# webcam.net
KiCad netlist of a schematic drawn in EAGLE
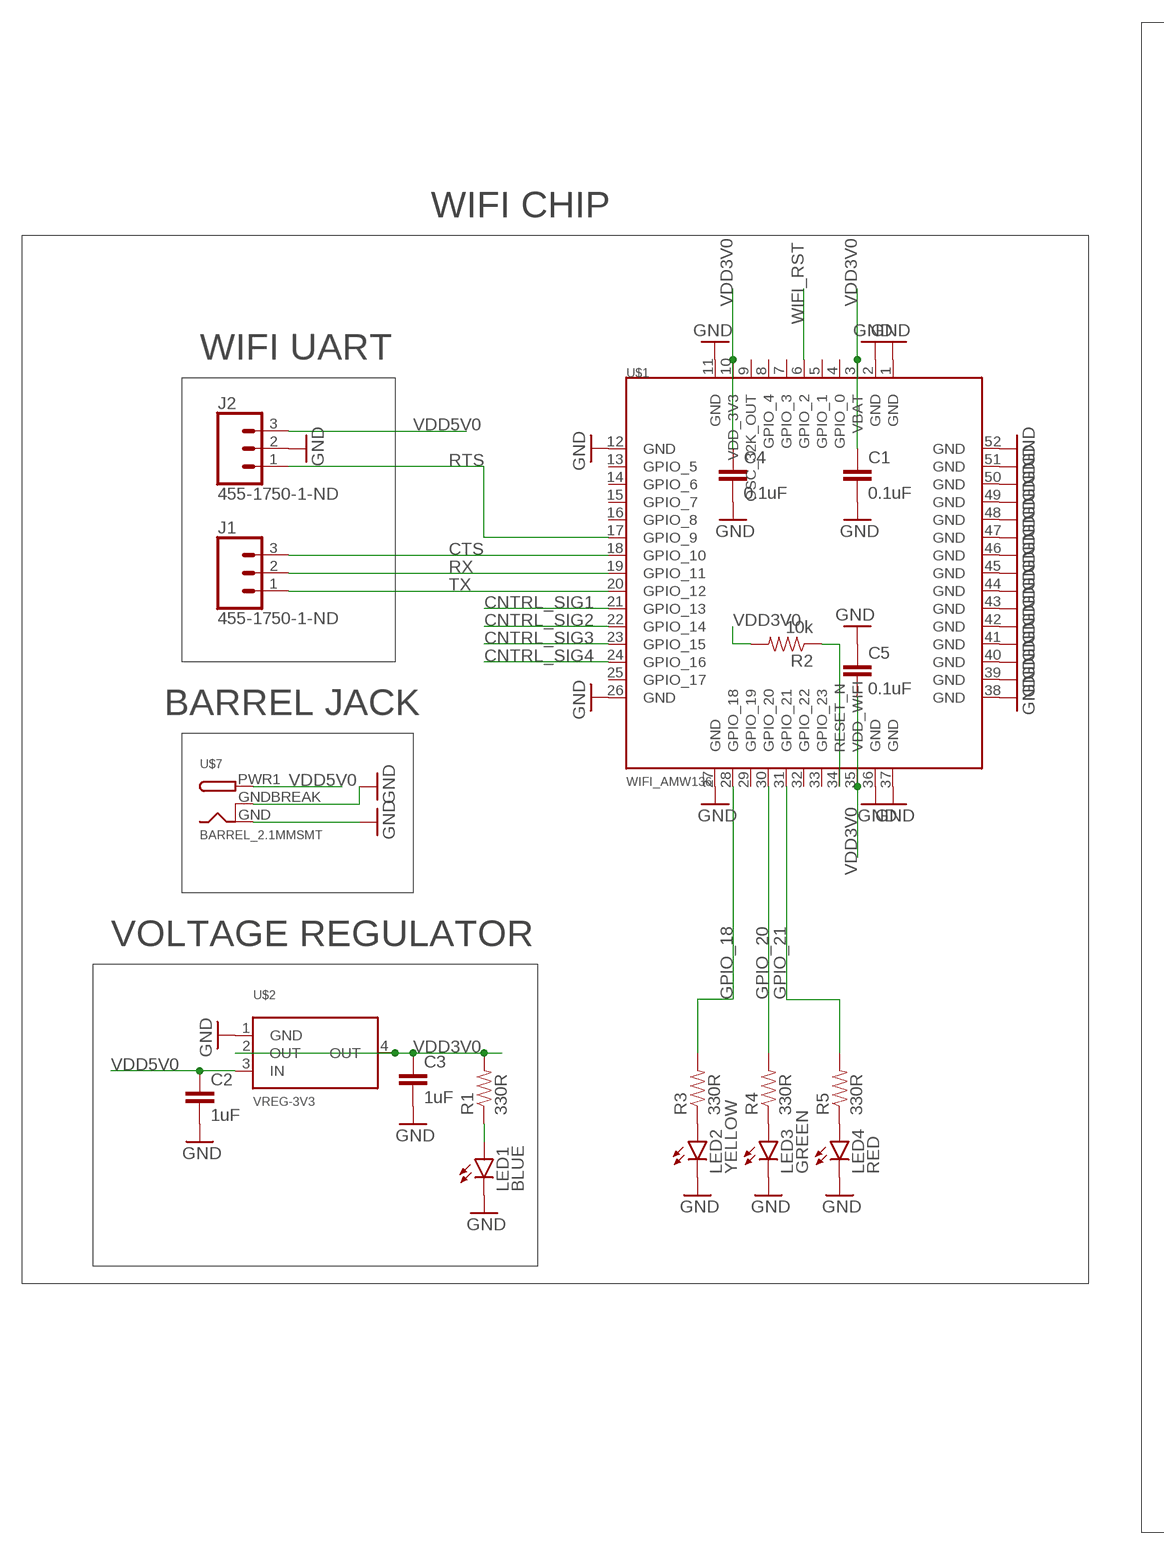
[diagram p0: schematic, sheet 1, part 1 of 2]
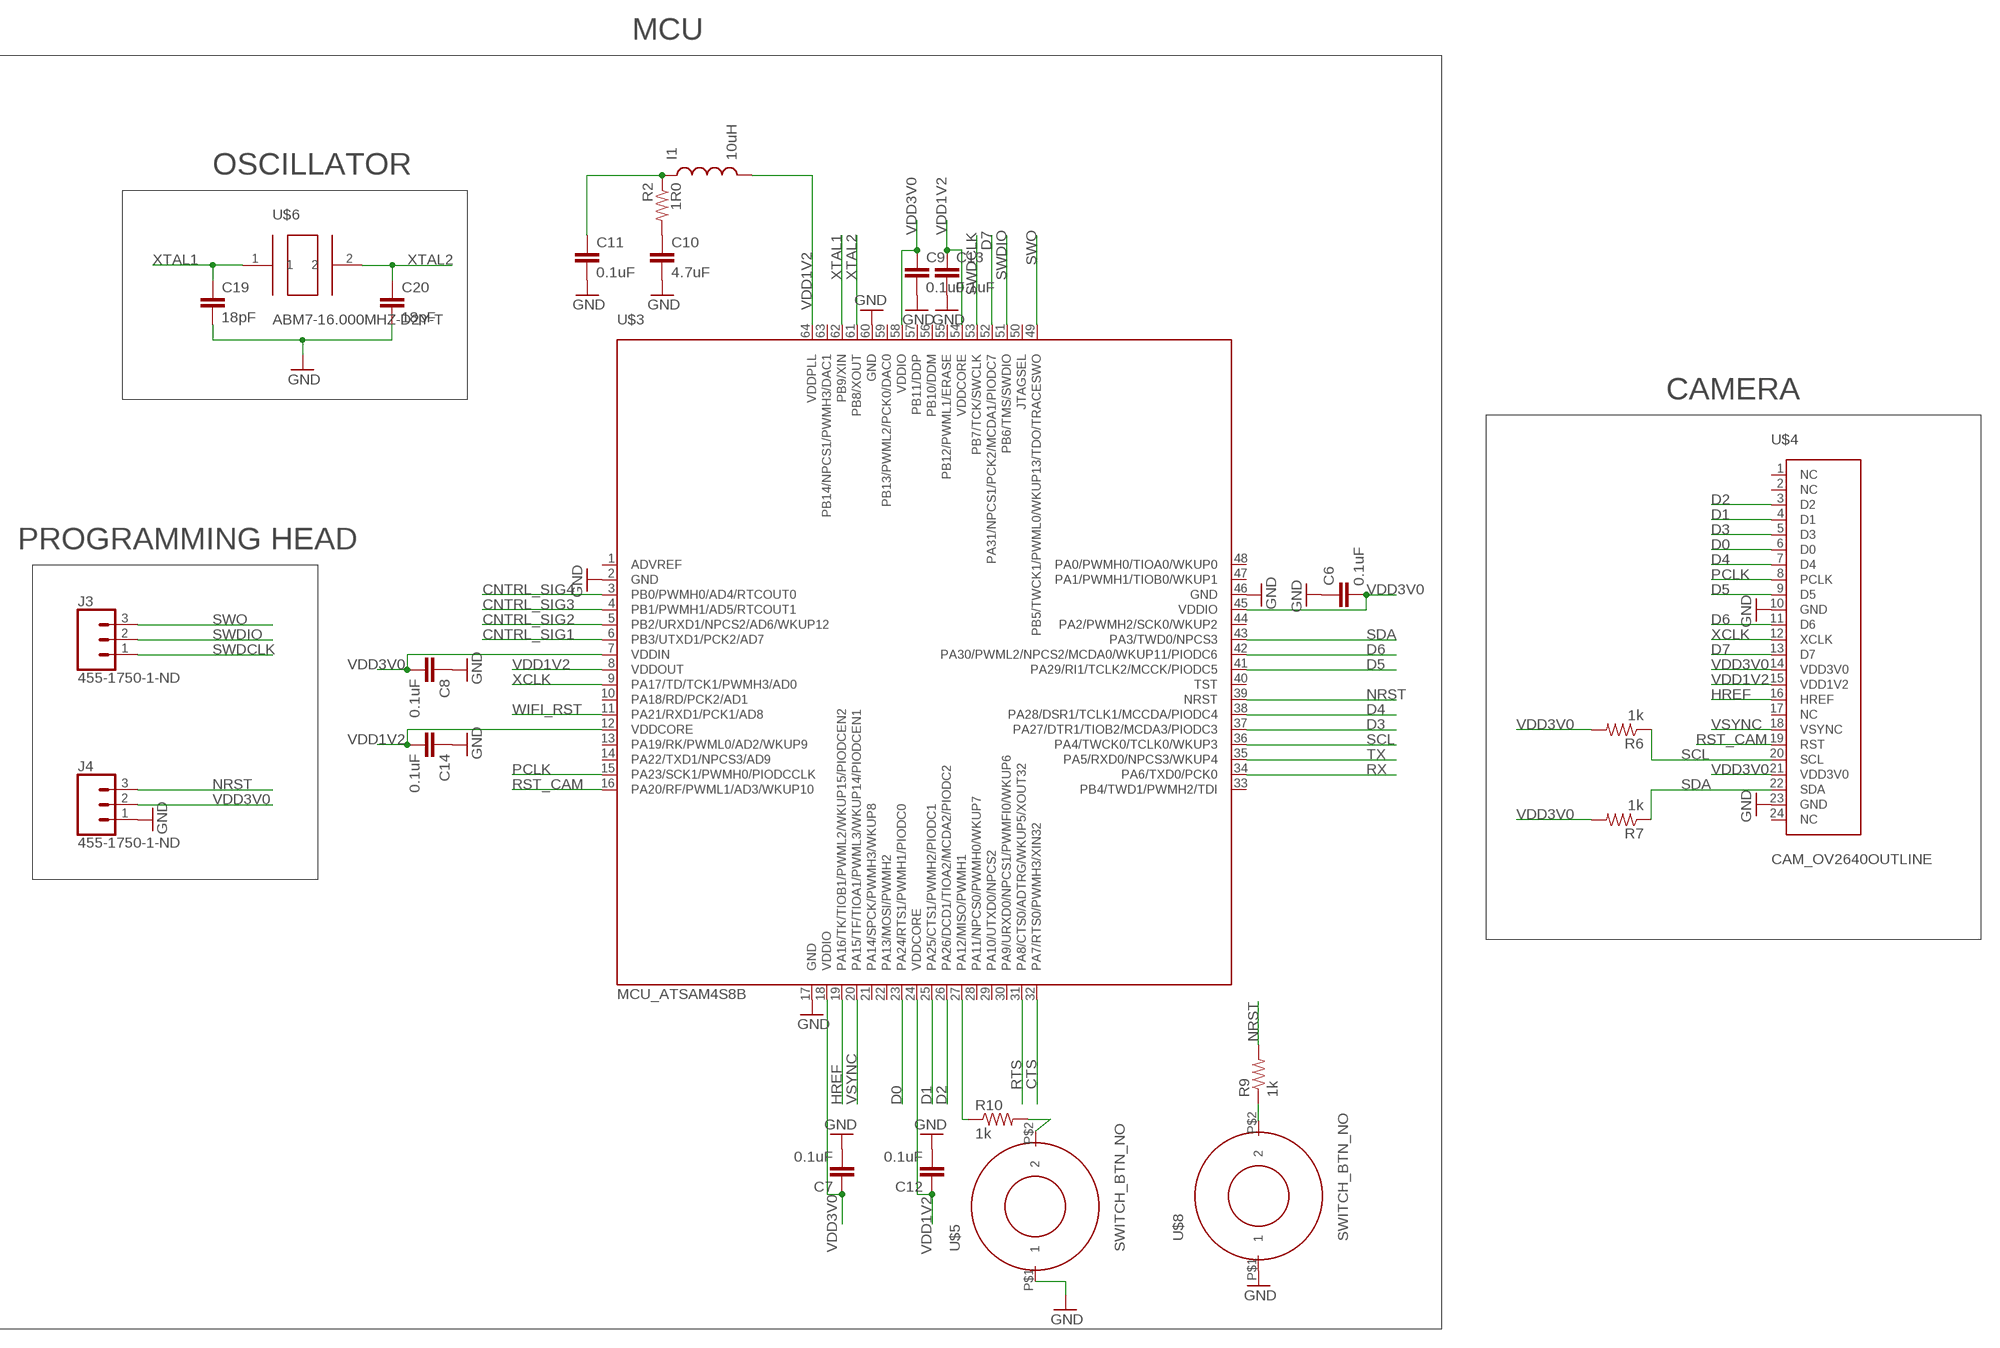
[diagram p1: schematic, sheet 1, part 2 of 2]

(export (version "E")
  (design (tool "Eeschema 10.0.6"))
  (components
    (comp (ref "1R0")
      (value "R2")
      (footprint "eagle-import:0805")
      (libsource (lib "eagle-import") (part "RES"))
    )
    (comp (ref "C1")
      (value "0.1uF")
      (footprint "eagle-import:0805")
      (libsource (lib "eagle-import") (part "CAP"))
    )
    (comp (ref "C2")
      (value "1uF")
      (footprint "eagle-import:0805")
      (libsource (lib "eagle-import") (part "CAP"))
    )
    (comp (ref "C3")
      (value "1uF")
      (footprint "eagle-import:0805")
      (libsource (lib "eagle-import") (part "CAP"))
    )
    (comp (ref "C4")
      (value "0.1uF")
      (footprint "eagle-import:0805")
      (libsource (lib "eagle-import") (part "CAP"))
    )
    (comp (ref "C5")
      (value "0.1uF")
      (footprint "eagle-import:0805")
      (libsource (lib "eagle-import") (part "CAP"))
    )
    (comp (ref "C6")
      (value "0.1uF")
      (footprint "eagle-import:0805")
      (libsource (lib "eagle-import") (part "CAP"))
    )
    (comp (ref "C7")
      (value "0.1uF")
      (footprint "eagle-import:0805")
      (libsource (lib "eagle-import") (part "CAP"))
    )
    (comp (ref "C8")
      (value "0.1uF")
      (footprint "eagle-import:0805")
      (libsource (lib "eagle-import") (part "CAP"))
    )
    (comp (ref "C9")
      (value "0.1uF")
      (footprint "eagle-import:0805")
      (libsource (lib "eagle-import") (part "CAP"))
    )
    (comp (ref "C10")
      (value "4.7uF")
      (footprint "eagle-import:0805")
      (libsource (lib "eagle-import") (part "CAP"))
    )
    (comp (ref "C11")
      (value "0.1uF")
      (footprint "eagle-import:0805")
      (libsource (lib "eagle-import") (part "CAP"))
    )
    (comp (ref "C12")
      (value "0.1uF")
      (footprint "eagle-import:0805")
      (libsource (lib "eagle-import") (part "CAP"))
    )
    (comp (ref "C13")
      (value "0.1uF")
      (footprint "eagle-import:0805")
      (libsource (lib "eagle-import") (part "CAP"))
    )
    (comp (ref "C14")
      (value "0.1uF")
      (footprint "eagle-import:0805")
      (libsource (lib "eagle-import") (part "CAP"))
    )
    (comp (ref "C19")
      (value "18pF")
      (footprint "eagle-import:0805")
      (libsource (lib "eagle-import") (part "CAP0805"))
    )
    (comp (ref "C20")
      (value "18pF")
      (footprint "eagle-import:0805")
      (libsource (lib "eagle-import") (part "CAP0805"))
    )
    (comp (ref "I1")
      (value "10uH")
      (footprint "eagle-import:0805")
      (fields (field (name "SPICEPREFIX") "I"))
      (libsource (lib "eagle-import") (part "IND"))
    )
    (comp (ref "J1")
      (value "455-1750-1-ND")
      (footprint "eagle-import:1X03")
      (libsource (lib "eagle-import") (part "CONN_03"))
    )
    (comp (ref "J2")
      (value "455-1750-1-ND")
      (footprint "eagle-import:1X03")
      (libsource (lib "eagle-import") (part "CONN_03"))
    )
    (comp (ref "J3")
      (value "455-1750-1-ND")
      (footprint "eagle-import:1X03")
      (libsource (lib "eagle-import") (part "CONN_03"))
    )
    (comp (ref "J4")
      (value "455-1750-1-ND")
      (footprint "eagle-import:1X03")
      (libsource (lib "eagle-import") (part "CONN_03"))
    )
    (comp (ref "LED1")
      (value "BLUE")
      (footprint "eagle-import:LED-0603")
      (libsource (lib "eagle-import") (part "LED0603"))
    )
    (comp (ref "LED2")
      (value "YELLOW")
      (footprint "eagle-import:LED-0603")
      (libsource (lib "eagle-import") (part "LED0603"))
    )
    (comp (ref "LED3")
      (value "GREEN")
      (footprint "eagle-import:LED-0603")
      (libsource (lib "eagle-import") (part "LED0603"))
    )
    (comp (ref "LED4")
      (value "RED")
      (footprint "eagle-import:LED-0603")
      (libsource (lib "eagle-import") (part "LED0603"))
    )
    (comp (ref "R1")
      (value "330R")
      (footprint "eagle-import:0805")
      (libsource (lib "eagle-import") (part "RES"))
    )
    (comp (ref "R2")
      (value "10k")
      (footprint "eagle-import:0805")
      (libsource (lib "eagle-import") (part "RES"))
    )
    (comp (ref "R3")
      (value "330R")
      (footprint "eagle-import:0805")
      (libsource (lib "eagle-import") (part "RES"))
    )
    (comp (ref "R4")
      (value "330R")
      (footprint "eagle-import:0805")
      (libsource (lib "eagle-import") (part "RES"))
    )
    (comp (ref "R5")
      (value "330R")
      (footprint "eagle-import:0805")
      (libsource (lib "eagle-import") (part "RES"))
    )
    (comp (ref "R6")
      (value "1k")
      (footprint "eagle-import:0805")
      (libsource (lib "eagle-import") (part "RES"))
    )
    (comp (ref "R7")
      (value "1k")
      (footprint "eagle-import:0805")
      (libsource (lib "eagle-import") (part "RES"))
    )
    (comp (ref "R9")
      (value "1k")
      (footprint "eagle-import:0805")
      (libsource (lib "eagle-import") (part "RES"))
    )
    (comp (ref "R10")
      (value "1k")
      (footprint "eagle-import:0805")
      (libsource (lib "eagle-import") (part "RES"))
    )
    (comp (ref "U$1")
      (value "WIFI_AMW136")
      (footprint "eagle-import:AMW136")
      (libsource (lib "eagle-import") (part "WIFI_AMW136"))
    )
    (comp (ref "U$2")
      (value "VREG-3V3")
      (footprint "eagle-import:R-PDSO-G4_TI")
      (libsource (lib "eagle-import") (part "VREG-3V3"))
    )
    (comp (ref "U$3")
      (value "MCU_ATSAM4S8B")
      (footprint "eagle-import:QFP50P1200X1200X160-64N")
      (libsource (lib "eagle-import") (part "MCU_ATSAM4S8B"))
    )
    (comp (ref "U$4")
      (value "CAM_OV2640OUTLINE")
      (footprint "eagle-import:CAM_CONN")
      (libsource (lib "eagle-import") (part "CAM_OV2640OUTLINE"))
    )
    (comp (ref "U$5")
      (value "SWITCH_BTN_NO")
      (footprint "eagle-import:BTN_2")
      (libsource (lib "eagle-import") (part "SWITCH_BTN_NO"))
    )
    (comp (ref "U$6")
      (value "ABM7-16.000MHZ-D2Y-T")
      (footprint "eagle-import:ABM7-16.000MHZ-D2Y-T")
      (libsource (lib "eagle-import") (part "ABM7-16.000MHZ-D2Y-T"))
    )
    (comp (ref "U$7")
      (value "BARREL_2.1MMSMT")
      (footprint "eagle-import:DCJACK_2MM_SMT")
      (libsource (lib "eagle-import") (part "BARREL_2.1MMSMT"))
    )
    (comp (ref "U$8")
      (value "SWITCH_BTN_NO")
      (footprint "eagle-import:BTN_2")
      (libsource (lib "eagle-import") (part "SWITCH_BTN_NO"))
    )
  )
  (nets
    (net (code "1") (name "/CNTRL_SIG1") (class "Default")
      (node (ref "U$1") (pin "21") (pinfunction "GPIO_13_21") (pintype "bidirectional"))
      (node (ref "U$3") (pin "6") (pinfunction "PB3/UTXD1/PCK2/AD7_6") (pintype "bidirectional"))
    )
    (net (code "2") (name "/CNTRL_SIG2") (class "Default")
      (node (ref "U$1") (pin "22") (pinfunction "GPIO_14_22") (pintype "bidirectional"))
      (node (ref "U$3") (pin "5") (pinfunction "PB2/URXD1/NPCS2/AD6/WKUP12_5") (pintype "bidirectional"))
    )
    (net (code "3") (name "/CNTRL_SIG3") (class "Default")
      (node (ref "U$1") (pin "23") (pinfunction "GPIO_15_23") (pintype "bidirectional"))
      (node (ref "U$3") (pin "4") (pinfunction "PB1/PWMH1/AD5/RTCOUT1_4") (pintype "bidirectional"))
    )
    (net (code "4") (name "/CNTRL_SIG4") (class "Default")
      (node (ref "U$1") (pin "24") (pinfunction "GPIO_16_24") (pintype "bidirectional"))
      (node (ref "U$3") (pin "3") (pinfunction "PB0/PWMH0/AD4/RTCOUT0_3") (pintype "bidirectional"))
    )
    (net (code "5") (name "/CTS") (class "Default")
      (node (ref "J1") (pin "3") (pinfunction "3_3") (pintype "passive"))
      (node (ref "U$1") (pin "18") (pinfunction "GPIO_10_18") (pintype "bidirectional"))
      (node (ref "U$3") (pin "32") (pinfunction "PA7/RTS0/PWMH3/XIN32_32") (pintype "bidirectional"))
    )
    (net (code "6") (name "/D0") (class "Default")
      (node (ref "U$3") (pin "23") (pinfunction "PA24/RTS1/PWMH1/PIODC0_23") (pintype "bidirectional"))
      (node (ref "U$4") (pin "6") (pinfunction "D0_6") (pintype "bidirectional"))
    )
    (net (code "7") (name "/D1") (class "Default")
      (node (ref "U$3") (pin "25") (pinfunction "PA25/CTS1/PWMH2/PIODC1_25") (pintype "bidirectional"))
      (node (ref "U$4") (pin "4") (pinfunction "D1_4") (pintype "bidirectional"))
    )
    (net (code "8") (name "/D2") (class "Default")
      (node (ref "U$3") (pin "26") (pinfunction "PA26/DCD1/TIOA2/MCDA2/PIODC2_26") (pintype "bidirectional"))
      (node (ref "U$4") (pin "3") (pinfunction "D2_3") (pintype "bidirectional"))
    )
    (net (code "9") (name "/D3") (class "Default")
      (node (ref "U$3") (pin "37") (pinfunction "PA27/DTR1/TIOB2/MCDA3/PIODC3_37") (pintype "bidirectional"))
      (node (ref "U$4") (pin "5") (pinfunction "D3_5") (pintype "bidirectional"))
    )
    (net (code "10") (name "/D4") (class "Default")
      (node (ref "U$3") (pin "38") (pinfunction "PA28/DSR1/TCLK1/MCCDA/PIODC4_38") (pintype "bidirectional"))
      (node (ref "U$4") (pin "7") (pinfunction "D4_7") (pintype "bidirectional"))
    )
    (net (code "11") (name "/D5") (class "Default")
      (node (ref "U$3") (pin "41") (pinfunction "PA29/RI1/TCLK2/MCCK/PIODC5_41") (pintype "bidirectional"))
      (node (ref "U$4") (pin "9") (pinfunction "D5_9") (pintype "bidirectional"))
    )
    (net (code "12") (name "/D6") (class "Default")
      (node (ref "U$3") (pin "42") (pinfunction "PA30/PWML2/NPCS2/MCDA0/WKUP11/PIODC6_42") (pintype "bidirectional"))
      (node (ref "U$4") (pin "11") (pinfunction "D6_11") (pintype "bidirectional"))
    )
    (net (code "13") (name "/D7") (class "Default")
      (node (ref "U$3") (pin "52") (pinfunction "PA31/NPCS1/PCK2/MCDA1/PIODC7_52") (pintype "bidirectional"))
      (node (ref "U$4") (pin "13") (pinfunction "D7_13") (pintype "bidirectional"))
    )
    (net (code "14") (name "/GPIO_18") (class "Default")
      (node (ref "R3") (pin "2") (pinfunction "2_2") (pintype "passive"))
      (node (ref "U$1") (pin "28") (pinfunction "GPIO_18_28") (pintype "bidirectional"))
    )
    (net (code "15") (name "/GPIO_20") (class "Default")
      (node (ref "R4") (pin "2") (pinfunction "2_2") (pintype "passive"))
      (node (ref "U$1") (pin "30") (pinfunction "GPIO_20_30") (pintype "bidirectional"))
    )
    (net (code "16") (name "/GPIO_21") (class "Default")
      (node (ref "R5") (pin "2") (pinfunction "2_2") (pintype "passive"))
      (node (ref "U$1") (pin "31") (pinfunction "GPIO_21_31") (pintype "bidirectional"))
    )
    (net (code "17") (name "/HREF") (class "Default")
      (node (ref "U$3") (pin "19") (pinfunction "PA16/TK/TIOB1/PWML2/WKUP15/PIODCEN2_19") (pintype "bidirectional"))
      (node (ref "U$4") (pin "16") (pinfunction "HREF_16") (pintype "bidirectional"))
    )
    (net (code "18") (name "/NRST") (class "Default")
      (node (ref "J4") (pin "3") (pinfunction "3_3") (pintype "passive"))
      (node (ref "R9") (pin "2") (pinfunction "2_2") (pintype "passive"))
      (node (ref "U$3") (pin "39") (pinfunction "NRST_39") (pintype "bidirectional"))
    )
    (net (code "19") (name "/PCLK") (class "Default")
      (node (ref "U$3") (pin "15") (pinfunction "PA23/SCK1/PWMH0/PIODCCLK_15") (pintype "bidirectional"))
      (node (ref "U$4") (pin "8") (pinfunction "PCLK_8") (pintype "bidirectional"))
    )
    (net (code "20") (name "/RST_CAM") (class "Default")
      (node (ref "U$3") (pin "16") (pinfunction "PA20/RF/PWML1/AD3/WKUP10_16") (pintype "bidirectional"))
      (node (ref "U$4") (pin "19") (pinfunction "RST_19") (pintype "bidirectional"))
    )
    (net (code "21") (name "/RTS") (class "Default")
      (node (ref "J2") (pin "1") (pinfunction "1_1") (pintype "passive"))
      (node (ref "U$1") (pin "17") (pinfunction "GPIO_9_17") (pintype "bidirectional"))
      (node (ref "U$3") (pin "31") (pinfunction "PA8/CTS0/ADTRG/WKUP5/XOUT32_31") (pintype "bidirectional"))
    )
    (net (code "22") (name "/RX") (class "Default")
      (node (ref "J1") (pin "2") (pinfunction "2_2") (pintype "passive"))
      (node (ref "U$1") (pin "19") (pinfunction "GPIO_11_19") (pintype "bidirectional"))
      (node (ref "U$3") (pin "34") (pinfunction "PA6/TXD0/PCK0_34") (pintype "bidirectional"))
    )
    (net (code "23") (name "/SCL") (class "Default")
      (node (ref "R6") (pin "1") (pinfunction "1_1") (pintype "passive"))
      (node (ref "U$3") (pin "36") (pinfunction "PA4/TWCK0/TCLK0/WKUP3_36") (pintype "bidirectional"))
      (node (ref "U$4") (pin "20") (pinfunction "SCL_20") (pintype "bidirectional"))
    )
    (net (code "24") (name "/SDA") (class "Default")
      (node (ref "R7") (pin "1") (pinfunction "1_1") (pintype "passive"))
      (node (ref "U$3") (pin "43") (pinfunction "PA3/TWD0/NPCS3_43") (pintype "bidirectional"))
      (node (ref "U$4") (pin "22") (pinfunction "SDA_22") (pintype "bidirectional"))
    )
    (net (code "25") (name "/SWDCLK") (class "Default")
      (node (ref "J3") (pin "1") (pinfunction "1_1") (pintype "passive"))
      (node (ref "U$3") (pin "53") (pinfunction "PB7/TCK/SWCLK_53") (pintype "bidirectional"))
    )
    (net (code "26") (name "/SWDIO") (class "Default")
      (node (ref "J3") (pin "2") (pinfunction "2_2") (pintype "passive"))
      (node (ref "U$3") (pin "51") (pinfunction "PB6/TMS/SWDIO_51") (pintype "bidirectional"))
    )
    (net (code "27") (name "/SWO") (class "Default")
      (node (ref "J3") (pin "3") (pinfunction "3_3") (pintype "passive"))
      (node (ref "U$3") (pin "49") (pinfunction "PB5/TWCK1/PWML0/WKUP13/TDO/TRACESWO_49") (pintype "bidirectional"))
    )
    (net (code "28") (name "/TX") (class "Default")
      (node (ref "J1") (pin "1") (pinfunction "1_1") (pintype "passive"))
      (node (ref "U$1") (pin "20") (pinfunction "GPIO_12_20") (pintype "bidirectional"))
      (node (ref "U$3") (pin "35") (pinfunction "PA5/RXD0/NPCS3/WKUP4_35") (pintype "bidirectional"))
    )
    (net (code "29") (name "/VDD1V2") (class "Default")
      (node (ref "C12") (pin "1") (pinfunction "1_1") (pintype "passive"))
      (node (ref "C13") (pin "1") (pinfunction "1_1") (pintype "passive"))
      (node (ref "C14") (pin "2") (pinfunction "2_2") (pintype "passive"))
      (node (ref "I1") (pin "2") (pinfunction "2_2") (pintype "passive"))
      (node (ref "U$3") (pin "12") (pinfunction "VDDCORE_12") (pintype "bidirectional"))
      (node (ref "U$3") (pin "24") (pinfunction "VDDCORE_24") (pintype "bidirectional"))
      (node (ref "U$3") (pin "54") (pinfunction "VDDCORE_54") (pintype "bidirectional"))
      (node (ref "U$3") (pin "64") (pinfunction "VDDPLL_64") (pintype "bidirectional"))
      (node (ref "U$3") (pin "8") (pinfunction "VDDOUT_8") (pintype "bidirectional"))
      (node (ref "U$4") (pin "15") (pinfunction "VDD1V2_15") (pintype "bidirectional"))
    )
    (net (code "30") (name "/VDD3V0") (class "Default")
      (node (ref "C1") (pin "1") (pinfunction "1_1") (pintype "passive"))
      (node (ref "C3") (pin "1") (pinfunction "1_1") (pintype "passive"))
      (node (ref "C4") (pin "1") (pinfunction "1_1") (pintype "passive"))
      (node (ref "C5") (pin "2") (pinfunction "2_2") (pintype "passive"))
      (node (ref "C6") (pin "2") (pinfunction "2_2") (pintype "passive"))
      (node (ref "C7") (pin "1") (pinfunction "1_1") (pintype "passive"))
      (node (ref "C8") (pin "2") (pinfunction "2_2") (pintype "passive"))
      (node (ref "C9") (pin "1") (pinfunction "1_1") (pintype "passive"))
      (node (ref "J4") (pin "2") (pinfunction "2_2") (pintype "passive"))
      (node (ref "R1") (pin "2") (pinfunction "2_2") (pintype "passive"))
      (node (ref "R2") (pin "2") (pinfunction "2_2") (pintype "passive"))
      (node (ref "R6") (pin "2") (pinfunction "2_2") (pintype "passive"))
      (node (ref "R7") (pin "2") (pinfunction "2_2") (pintype "passive"))
      (node (ref "U$1") (pin "10") (pinfunction "VDD_3V3_10") (pintype "bidirectional"))
      (node (ref "U$1") (pin "3") (pinfunction "VBAT_3") (pintype "bidirectional"))
      (node (ref "U$1") (pin "35") (pinfunction "VDD_WIFI_35") (pintype "bidirectional"))
      (node (ref "U$2") (pin "2") (pinfunction "OUT_2") (pintype "bidirectional"))
      (node (ref "U$2") (pin "4") (pinfunction "OUT_4") (pintype "bidirectional"))
      (node (ref "U$3") (pin "18") (pinfunction "VDDIO_18") (pintype "bidirectional"))
      (node (ref "U$3") (pin "45") (pinfunction "VDDIO_45") (pintype "bidirectional"))
      (node (ref "U$3") (pin "58") (pinfunction "VDDIO_58") (pintype "bidirectional"))
      (node (ref "U$3") (pin "7") (pinfunction "VDDIN_7") (pintype "bidirectional"))
      (node (ref "U$4") (pin "14") (pinfunction "VDD3V0_14") (pintype "bidirectional"))
      (node (ref "U$4") (pin "21") (pinfunction "VDD3V0_21") (pintype "bidirectional"))
    )
    (net (code "31") (name "/VDD5V0") (class "Default")
      (node (ref "C2") (pin "1") (pinfunction "1_1") (pintype "passive"))
      (node (ref "J2") (pin "3") (pinfunction "3_3") (pintype "passive"))
      (node (ref "U$2") (pin "3") (pinfunction "IN_3") (pintype "bidirectional"))
      (node (ref "U$7") (pin "PWR1") (pinfunction "PWR_PWR1") (pintype "power_in"))
    )
    (net (code "32") (name "/VSYNC") (class "Default")
      (node (ref "U$3") (pin "20") (pinfunction "PA15/TF/TIOA1/PWML3/WKUP14/PIODCEN1_20") (pintype "bidirectional"))
      (node (ref "U$4") (pin "18") (pinfunction "VSYNC_18") (pintype "bidirectional"))
    )
    (net (code "33") (name "/WIFI_RST") (class "Default")
      (node (ref "U$1") (pin "6") (pinfunction "GPIO_2_6") (pintype "bidirectional"))
      (node (ref "U$3") (pin "11") (pinfunction "PA21/RXD1/PCK1/AD8_11") (pintype "bidirectional"))
    )
    (net (code "34") (name "/XCLK") (class "Default")
      (node (ref "U$3") (pin "9") (pinfunction "PA17/TD/TCK1/PWMH3/AD0_9") (pintype "bidirectional"))
      (node (ref "U$4") (pin "12") (pinfunction "XCLK_12") (pintype "bidirectional"))
    )
    (net (code "35") (name "/XTAL1") (class "Default")
      (node (ref "C19") (pin "1") (pinfunction "1_1") (pintype "passive"))
      (node (ref "U$3") (pin "62") (pinfunction "PB9/XIN_62") (pintype "bidirectional"))
      (node (ref "U$6") (pin "1") (pinfunction "1_1") (pintype "bidirectional"))
    )
    (net (code "36") (name "/XTAL2") (class "Default")
      (node (ref "C20") (pin "1") (pinfunction "1_1") (pintype "passive"))
      (node (ref "U$3") (pin "61") (pinfunction "PB8/XOUT_61") (pintype "bidirectional"))
      (node (ref "U$6") (pin "2") (pinfunction "2_2") (pintype "bidirectional"))
    )
    (net (code "37") (name "GND") (class "Default")
      (node (ref "C1") (pin "2") (pinfunction "2_2") (pintype "passive"))
      (node (ref "C10") (pin "2") (pinfunction "2_2") (pintype "passive"))
      (node (ref "C11") (pin "2") (pinfunction "2_2") (pintype "passive"))
      (node (ref "C12") (pin "2") (pinfunction "2_2") (pintype "passive"))
      (node (ref "C13") (pin "2") (pinfunction "2_2") (pintype "passive"))
      (node (ref "C14") (pin "1") (pinfunction "1_1") (pintype "passive"))
      (node (ref "C19") (pin "2") (pinfunction "2_2") (pintype "passive"))
      (node (ref "C2") (pin "2") (pinfunction "2_2") (pintype "passive"))
      (node (ref "C20") (pin "2") (pinfunction "2_2") (pintype "passive"))
      (node (ref "C3") (pin "2") (pinfunction "2_2") (pintype "passive"))
      (node (ref "C4") (pin "2") (pinfunction "2_2") (pintype "passive"))
      (node (ref "C5") (pin "1") (pinfunction "1_1") (pintype "passive"))
      (node (ref "C6") (pin "1") (pinfunction "1_1") (pintype "passive"))
      (node (ref "C7") (pin "2") (pinfunction "2_2") (pintype "passive"))
      (node (ref "C8") (pin "1") (pinfunction "1_1") (pintype "passive"))
      (node (ref "C9") (pin "2") (pinfunction "2_2") (pintype "passive"))
      (node (ref "J2") (pin "2") (pinfunction "2_2") (pintype "passive"))
      (node (ref "J4") (pin "1") (pinfunction "1_1") (pintype "passive"))
      (node (ref "LED1") (pin "C") (pinfunction "C_C") (pintype "passive"))
      (node (ref "LED2") (pin "C") (pinfunction "C_C") (pintype "passive"))
      (node (ref "LED3") (pin "C") (pinfunction "C_C") (pintype "passive"))
      (node (ref "LED4") (pin "C") (pinfunction "C_C") (pintype "passive"))
      (node (ref "U$1") (pin "1") (pinfunction "GND_1") (pintype "bidirectional"))
      (node (ref "U$1") (pin "11") (pinfunction "GND_11") (pintype "bidirectional"))
      (node (ref "U$1") (pin "12") (pinfunction "GND_12") (pintype "bidirectional"))
      (node (ref "U$1") (pin "2") (pinfunction "GND_2") (pintype "bidirectional"))
      (node (ref "U$1") (pin "26") (pinfunction "GND_26") (pintype "bidirectional"))
      (node (ref "U$1") (pin "27") (pinfunction "GND_27") (pintype "bidirectional"))
      (node (ref "U$1") (pin "36") (pinfunction "GND_36") (pintype "bidirectional"))
      (node (ref "U$1") (pin "37") (pinfunction "GND_37") (pintype "bidirectional"))
      (node (ref "U$1") (pin "38") (pinfunction "GND_38") (pintype "bidirectional"))
      (node (ref "U$1") (pin "39") (pinfunction "GND_39") (pintype "bidirectional"))
      (node (ref "U$1") (pin "40") (pinfunction "GND_40") (pintype "bidirectional"))
      (node (ref "U$1") (pin "41") (pinfunction "GND_41") (pintype "bidirectional"))
      (node (ref "U$1") (pin "42") (pinfunction "GND_42") (pintype "bidirectional"))
      (node (ref "U$1") (pin "43") (pinfunction "GND_43") (pintype "bidirectional"))
      (node (ref "U$1") (pin "44") (pinfunction "GND_44") (pintype "bidirectional"))
      (node (ref "U$1") (pin "45") (pinfunction "GND_45") (pintype "bidirectional"))
      (node (ref "U$1") (pin "46") (pinfunction "GND_46") (pintype "bidirectional"))
      (node (ref "U$1") (pin "47") (pinfunction "GND_47") (pintype "bidirectional"))
      (node (ref "U$1") (pin "48") (pinfunction "GND_48") (pintype "bidirectional"))
      (node (ref "U$1") (pin "49") (pinfunction "GND_49") (pintype "bidirectional"))
      (node (ref "U$1") (pin "50") (pinfunction "GND_50") (pintype "bidirectional"))
      (node (ref "U$1") (pin "51") (pinfunction "GND_51") (pintype "bidirectional"))
      (node (ref "U$1") (pin "52") (pinfunction "GND_52") (pintype "bidirectional"))
      (node (ref "U$2") (pin "1") (pinfunction "GND_1") (pintype "bidirectional"))
      (node (ref "U$3") (pin "17") (pinfunction "GND_17") (pintype "bidirectional"))
      (node (ref "U$3") (pin "2") (pinfunction "GND_2") (pintype "bidirectional"))
      (node (ref "U$3") (pin "46") (pinfunction "GND_46") (pintype "bidirectional"))
      (node (ref "U$3") (pin "60") (pinfunction "GND_60") (pintype "bidirectional"))
      (node (ref "U$4") (pin "10") (pinfunction "GND_10") (pintype "bidirectional"))
      (node (ref "U$4") (pin "23") (pinfunction "GND_23") (pintype "bidirectional"))
      (node (ref "U$5") (pin "P$1") (pinfunction "1_P$1") (pintype "bidirectional"))
      (node (ref "U$7") (pin "GND") (pinfunction "GND_GND") (pintype "power_in"))
      (node (ref "U$7") (pin "GNDBREAK") (pinfunction "GNDBREAK_GNDBREAK") (pintype "power_in"))
      (node (ref "U$8") (pin "P$1") (pinfunction "1_P$1") (pintype "bidirectional"))
    )
    (net (code "38") (name "Net-(1R0-Pad1)") (class "Default")
      (node (ref "1R0") (pin "1") (pinfunction "1_1") (pintype "passive"))
      (node (ref "C11") (pin "1") (pinfunction "1_1") (pintype "passive"))
      (node (ref "I1") (pin "1") (pinfunction "1_1") (pintype "passive"))
    )
    (net (code "39") (name "Net-(1R0-Pad2)") (class "Default")
      (node (ref "1R0") (pin "2") (pinfunction "2_2") (pintype "passive"))
      (node (ref "C10") (pin "1") (pinfunction "1_1") (pintype "passive"))
    )
    (net (code "40") (name "Net-(LED1-PadA)") (class "Default")
      (node (ref "LED1") (pin "A") (pinfunction "A_A") (pintype "passive"))
      (node (ref "R1") (pin "1") (pinfunction "1_1") (pintype "passive"))
    )
    (net (code "41") (name "Net-(LED2-PadA)") (class "Default")
      (node (ref "LED2") (pin "A") (pinfunction "A_A") (pintype "passive"))
      (node (ref "R3") (pin "1") (pinfunction "1_1") (pintype "passive"))
    )
    (net (code "42") (name "Net-(LED3-PadA)") (class "Default")
      (node (ref "LED3") (pin "A") (pinfunction "A_A") (pintype "passive"))
      (node (ref "R4") (pin "1") (pinfunction "1_1") (pintype "passive"))
    )
    (net (code "43") (name "Net-(LED4-PadA)") (class "Default")
      (node (ref "LED4") (pin "A") (pinfunction "A_A") (pintype "passive"))
      (node (ref "R5") (pin "1") (pinfunction "1_1") (pintype "passive"))
    )
    (net (code "44") (name "Net-(U$1-RESET_N)") (class "Default")
      (node (ref "R2") (pin "1") (pinfunction "1_1") (pintype "passive"))
      (node (ref "U$1") (pin "34") (pinfunction "RESET_N_34") (pintype "bidirectional"))
    )
    (net (code "45") (name "Net-(U$3-PA12{slash}MISO{slash}PWMH1)") (class "Default")
      (node (ref "R10") (pin "1") (pinfunction "1_1") (pintype "passive"))
      (node (ref "U$3") (pin "27") (pinfunction "PA12/MISO/PWMH1_27") (pintype "bidirectional"))
    )
    (net (code "46") (name "Net-(U$5-2)") (class "Default")
      (node (ref "R10") (pin "2") (pinfunction "2_2") (pintype "passive"))
      (node (ref "U$5") (pin "P$2") (pinfunction "2_P$2") (pintype "bidirectional"))
    )
    (net (code "47") (name "Net-(U$8-2)") (class "Default")
      (node (ref "R9") (pin "1") (pinfunction "1_1") (pintype "passive"))
      (node (ref "U$8") (pin "P$2") (pinfunction "2_P$2") (pintype "bidirectional"))
    )
    (net (code "48") (name "unconnected-(U$1-GPIO_0-Pad4)") (class "Default")
      (node (ref "U$1") (pin "4") (pinfunction "GPIO_0_4") (pintype "bidirectional"))
    )
    (net (code "49") (name "unconnected-(U$1-GPIO_1-Pad5)") (class "Default")
      (node (ref "U$1") (pin "5") (pinfunction "GPIO_1_5") (pintype "bidirectional"))
    )
    (net (code "50") (name "unconnected-(U$1-GPIO_3-Pad7)") (class "Default")
      (node (ref "U$1") (pin "7") (pinfunction "GPIO_3_7") (pintype "bidirectional"))
    )
    (net (code "51") (name "unconnected-(U$1-GPIO_4-Pad8)") (class "Default")
      (node (ref "U$1") (pin "8") (pinfunction "GPIO_4_8") (pintype "bidirectional"))
    )
    (net (code "52") (name "unconnected-(U$1-GPIO_5-Pad13)") (class "Default")
      (node (ref "U$1") (pin "13") (pinfunction "GPIO_5_13") (pintype "bidirectional"))
    )
    (net (code "53") (name "unconnected-(U$1-GPIO_6-Pad14)") (class "Default")
      (node (ref "U$1") (pin "14") (pinfunction "GPIO_6_14") (pintype "bidirectional"))
    )
    (net (code "54") (name "unconnected-(U$1-GPIO_7-Pad15)") (class "Default")
      (node (ref "U$1") (pin "15") (pinfunction "GPIO_7_15") (pintype "bidirectional"))
    )
    (net (code "55") (name "unconnected-(U$1-GPIO_8-Pad16)") (class "Default")
      (node (ref "U$1") (pin "16") (pinfunction "GPIO_8_16") (pintype "bidirectional"))
    )
    (net (code "56") (name "unconnected-(U$1-GPIO_17-Pad25)") (class "Default")
      (node (ref "U$1") (pin "25") (pinfunction "GPIO_17_25") (pintype "bidirectional"))
    )
    (net (code "57") (name "unconnected-(U$1-GPIO_19-Pad29)") (class "Default")
      (node (ref "U$1") (pin "29") (pinfunction "GPIO_19_29") (pintype "bidirectional"))
    )
    (net (code "58") (name "unconnected-(U$1-GPIO_22-Pad32)") (class "Default")
      (node (ref "U$1") (pin "32") (pinfunction "GPIO_22_32") (pintype "bidirectional"))
    )
    (net (code "59") (name "unconnected-(U$1-GPIO_23-Pad33)") (class "Default")
      (node (ref "U$1") (pin "33") (pinfunction "GPIO_23_33") (pintype "bidirectional"))
    )
    (net (code "60") (name "unconnected-(U$1-OSC_32K_OUT-Pad9)") (class "Default")
      (node (ref "U$1") (pin "9") (pinfunction "OSC_32K_OUT_9") (pintype "bidirectional"))
    )
    (net (code "61") (name "unconnected-(U$3-ADVREF-Pad1)") (class "Default")
      (node (ref "U$3") (pin "1") (pinfunction "ADVREF_1") (pintype "bidirectional"))
    )
    (net (code "62") (name "unconnected-(U$3-JTAGSEL-Pad50)") (class "Default")
      (node (ref "U$3") (pin "50") (pinfunction "JTAGSEL_50") (pintype "bidirectional"))
    )
    (net (code "63") (name "unconnected-(U$3-PA0{slash}PWMH0{slash}TIOA0{slash}WKUP0-Pad48)") (class "Default")
      (node (ref "U$3") (pin "48") (pinfunction "PA0/PWMH0/TIOA0/WKUP0_48") (pintype "bidirectional"))
    )
    (net (code "64") (name "unconnected-(U$3-PA1{slash}PWMH1{slash}TIOB0{slash}WKUP1-Pad47)") (class "Default")
      (node (ref "U$3") (pin "47") (pinfunction "PA1/PWMH1/TIOB0/WKUP1_47") (pintype "bidirectional"))
    )
    (net (code "65") (name "unconnected-(U$3-PA2{slash}PWMH2{slash}SCK0{slash}WKUP2-Pad44)") (class "Default")
      (node (ref "U$3") (pin "44") (pinfunction "PA2/PWMH2/SCK0/WKUP2_44") (pintype "bidirectional"))
    )
    (net (code "66") (name "unconnected-(U$3-PA9{slash}URXD0{slash}NPCS1{slash}PWMFI0{slash}WKUP6-Pad30)") (class "Default")
      (node (ref "U$3") (pin "30") (pinfunction "PA9/URXD0/NPCS1/PWMFI0/WKUP6_30") (pintype "bidirectional"))
    )
    (net (code "67") (name "unconnected-(U$3-PA10{slash}UTXD0{slash}NPCS2-Pad29)") (class "Default")
      (node (ref "U$3") (pin "29") (pinfunction "PA10/UTXD0/NPCS2_29") (pintype "bidirectional"))
    )
    (net (code "68") (name "unconnected-(U$3-PA11{slash}NPCS0{slash}PWMH0{slash}WKUP7-Pad28)") (class "Default")
      (node (ref "U$3") (pin "28") (pinfunction "PA11/NPCS0/PWMH0/WKUP7_28") (pintype "bidirectional"))
    )
    (net (code "69") (name "unconnected-(U$3-PA13{slash}MOSI{slash}PWMH2-Pad22)") (class "Default")
      (node (ref "U$3") (pin "22") (pinfunction "PA13/MOSI/PWMH2_22") (pintype "bidirectional"))
    )
    (net (code "70") (name "unconnected-(U$3-PA14{slash}SPCK{slash}PWMH3{slash}WKUP8-Pad21)") (class "Default")
      (node (ref "U$3") (pin "21") (pinfunction "PA14/SPCK/PWMH3/WKUP8_21") (pintype "bidirectional"))
    )
    (net (code "71") (name "unconnected-(U$3-PA18{slash}RD{slash}PCK2{slash}AD1-Pad10)") (class "Default")
      (node (ref "U$3") (pin "10") (pinfunction "PA18/RD/PCK2/AD1_10") (pintype "bidirectional"))
    )
    (net (code "72") (name "unconnected-(U$3-PA19{slash}RK{slash}PWML0{slash}AD2{slash}WKUP9-Pad13)") (class "Default")
      (node (ref "U$3") (pin "13") (pinfunction "PA19/RK/PWML0/AD2/WKUP9_13") (pintype "bidirectional"))
    )
    (net (code "73") (name "unconnected-(U$3-PA22{slash}TXD1{slash}NPCS3{slash}AD9-Pad14)") (class "Default")
      (node (ref "U$3") (pin "14") (pinfunction "PA22/TXD1/NPCS3/AD9_14") (pintype "bidirectional"))
    )
    (net (code "74") (name "unconnected-(U$3-PB4{slash}TWD1{slash}PWMH2{slash}TDI-Pad33)") (class "Default")
      (node (ref "U$3") (pin "33") (pinfunction "PB4/TWD1/PWMH2/TDI_33") (pintype "bidirectional"))
    )
    (net (code "75") (name "unconnected-(U$3-PB10{slash}DDM-Pad56)") (class "Default")
      (node (ref "U$3") (pin "56") (pinfunction "PB10/DDM_56") (pintype "bidirectional"))
    )
    (net (code "76") (name "unconnected-(U$3-PB11{slash}DDP-Pad57)") (class "Default")
      (node (ref "U$3") (pin "57") (pinfunction "PB11/DDP_57") (pintype "bidirectional"))
    )
    (net (code "77") (name "unconnected-(U$3-PB12{slash}PWML1{slash}ERASE-Pad55)") (class "Default")
      (node (ref "U$3") (pin "55") (pinfunction "PB12/PWML1/ERASE_55") (pintype "bidirectional"))
    )
    (net (code "78") (name "unconnected-(U$3-PB13{slash}PWML2{slash}PCK0{slash}DAC0-Pad59)") (class "Default")
      (node (ref "U$3") (pin "59") (pinfunction "PB13/PWML2/PCK0/DAC0_59") (pintype "bidirectional"))
    )
    (net (code "79") (name "unconnected-(U$3-PB14{slash}NPCS1{slash}PWMH3{slash}DAC1-Pad63)") (class "Default")
      (node (ref "U$3") (pin "63") (pinfunction "PB14/NPCS1/PWMH3/DAC1_63") (pintype "bidirectional"))
    )
    (net (code "80") (name "unconnected-(U$3-TST-Pad40)") (class "Default")
      (node (ref "U$3") (pin "40") (pinfunction "TST_40") (pintype "bidirectional"))
    )
    (net (code "81") (name "unconnected-(U$4-NC-Pad1)") (class "Default")
      (node (ref "U$4") (pin "1") (pinfunction "NC_1") (pintype "bidirectional"))
    )
    (net (code "82") (name "unconnected-(U$4-NC-Pad2)") (class "Default")
      (node (ref "U$4") (pin "2") (pinfunction "NC_2") (pintype "bidirectional"))
    )
    (net (code "83") (name "unconnected-(U$4-NC-Pad17)") (class "Default")
      (node (ref "U$4") (pin "17") (pinfunction "NC_17") (pintype "bidirectional"))
    )
    (net (code "84") (name "unconnected-(U$4-NC-Pad24)") (class "Default")
      (node (ref "U$4") (pin "24") (pinfunction "NC_24") (pintype "bidirectional"))
    )
  )
)
